# STMod.net
KiCad netlist of a schematic drawn in Altium Designer
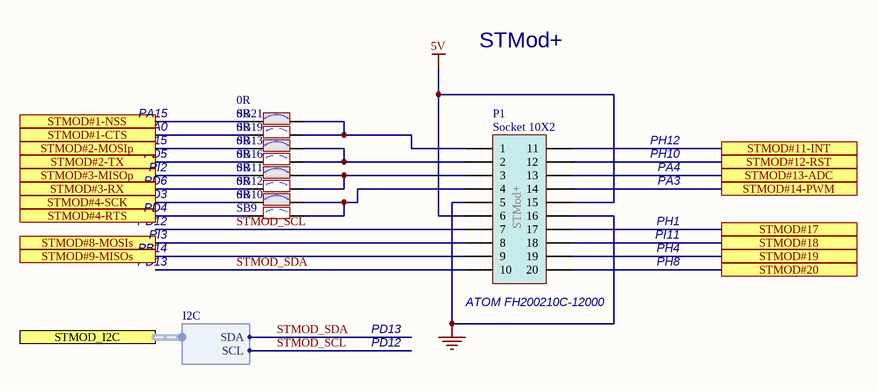
[diagram p0: STMod+.SchDoc]

(export (version "E")
  (design (tool "Eeschema 10.0.6"))
  (components
    (comp (ref "P1")
      (value "Socket 10X2")
      (footprint "CON_SAMTEC_SQT-110-01-F-D-RA__STMOD+")
      (description "Socket 10x2, 2.00mm, RA, TH, Height 6.35mm/2.29mm")
      (fields
        (field (name "INTERNAL_PART_NUMBER") "MCD-00309")
        (field (name "MANUFACTURER_PART_NUMBER") "SQT-110-01-F-D-RA")
        (field (name "PROVIDED_BY") "SubCon")
      )
      (libsource (lib "MCD_PARTS_database") (part "Socket 10X2 STMod+"))
    )
    (comp (ref "SB9")
      (value "0R")
      (footprint "SOLDER-BRIDGE_R0603-0R")
      (description "Solder Bridge OFF")
      (fields (field (name "INTERNAL_PART_NUMBER") "MCD-00072") (field (name "MANUFACTURER") "YAGEO"))
      (libsource (lib "MCD_PARTS_database") (part "SB_OFF"))
    )
    (comp (ref "SB10")
      (value "0R")
      (footprint "SOLDER-BRIDGE_R0603-0R")
      (description "Solder Bridge ON")
      (fields
        (field (name "INTERNAL_PART_NUMBER") "MCD-00071")
        (field (name "MANUFACTURER") "YAGEO")
        (field (name "PROVIDED_BY") "Subcon")
      )
      (libsource (lib "MCD_PARTS_database") (part "SB_ON"))
    )
    (comp (ref "SB11")
      (value "0R")
      (footprint "SOLDER-BRIDGE_R0603-0R")
      (description "Solder Bridge ON")
      (fields
        (field (name "INTERNAL_PART_NUMBER") "MCD-00071")
        (field (name "MANUFACTURER") "YAGEO")
        (field (name "PROVIDED_BY") "Subcon")
      )
      (libsource (lib "MCD_PARTS_database") (part "SB_ON"))
    )
    (comp (ref "SB12")
      (value "0R")
      (footprint "SOLDER-BRIDGE_R0603-0R")
      (description "Solder Bridge OFF")
      (fields (field (name "INTERNAL_PART_NUMBER") "MCD-00072") (field (name "MANUFACTURER") "YAGEO"))
      (libsource (lib "MCD_PARTS_database") (part "SB_OFF"))
    )
    (comp (ref "SB13")
      (value "0R")
      (footprint "SOLDER-BRIDGE_R0603-0R")
      (description "Solder Bridge ON")
      (fields
        (field (name "INTERNAL_PART_NUMBER") "MCD-00071")
        (field (name "MANUFACTURER") "YAGEO")
        (field (name "PROVIDED_BY") "Subcon")
      )
      (libsource (lib "MCD_PARTS_database") (part "SB_ON"))
    )
    (comp (ref "SB16")
      (value "0R")
      (footprint "SOLDER-BRIDGE_R0603-0R")
      (description "Solder Bridge OFF")
      (fields (field (name "INTERNAL_PART_NUMBER") "MCD-00072") (field (name "MANUFACTURER") "YAGEO"))
      (libsource (lib "MCD_PARTS_database") (part "SB_OFF"))
    )
    (comp (ref "SB19")
      (value "0R")
      (footprint "SOLDER-BRIDGE_R0603-0R")
      (description "Solder Bridge OFF")
      (fields (field (name "INTERNAL_PART_NUMBER") "MCD-00072") (field (name "MANUFACTURER") "YAGEO"))
      (libsource (lib "MCD_PARTS_database") (part "SB_OFF"))
    )
    (comp (ref "SB21")
      (value "0R")
      (footprint "SOLDER-BRIDGE_R0603-0R")
      (description "Solder Bridge ON")
      (fields
        (field (name "INTERNAL_PART_NUMBER") "MCD-00071")
        (field (name "MANUFACTURER") "YAGEO")
        (field (name "PROVIDED_BY") "Subcon")
      )
      (libsource (lib "MCD_PARTS_database") (part "SB_ON"))
    )
  )
  (nets
    (net (code "2") (name "/STMOD#1-CTS") (class "Default")
      (node (ref "SB19") (pin "1") (pinfunction "1_1") (pintype "passive"))
    )
    (net (code "3") (name "/STMOD#1-NSS") (class "Default")
      (node (ref "SB21") (pin "1") (pinfunction "1_1") (pintype "passive"))
    )
    (net (code "4") (name "/STMOD#2-MOSIp") (class "Default")
      (node (ref "SB13") (pin "1") (pinfunction "1_1") (pintype "passive"))
    )
    (net (code "5") (name "/STMOD#2-TX") (class "Default")
      (node (ref "SB16") (pin "1") (pinfunction "1_1") (pintype "passive"))
    )
    (net (code "6") (name "/STMOD#3-MISOp") (class "Default")
      (node (ref "SB11") (pin "1") (pinfunction "1_1") (pintype "passive"))
    )
    (net (code "7") (name "/STMOD#3-RX") (class "Default")
      (node (ref "SB12") (pin "1") (pinfunction "1_1") (pintype "passive"))
    )
    (net (code "8") (name "/STMOD#4-RTS") (class "Default")
      (node (ref "SB9") (pin "1") (pinfunction "1_1") (pintype "passive"))
    )
    (net (code "9") (name "/STMOD#4-SCK") (class "Default")
      (node (ref "SB10") (pin "1") (pinfunction "1_1") (pintype "passive"))
    )
    (net (code "10") (name "/STMOD#8-MOSIs") (class "Default")
      (node (ref "P1") (pin "8") (pinfunction "8_8") (pintype "passive"))
    )
    (net (code "11") (name "/STMOD#9-MISOs") (class "Default")
      (node (ref "P1") (pin "9") (pinfunction "9_9") (pintype "passive"))
    )
    (net (code "12") (name "/STMOD#11-INT") (class "Default")
      (node (ref "P1") (pin "11") (pinfunction "11_11") (pintype "passive"))
    )
    (net (code "13") (name "/STMOD#12-RST") (class "Default")
      (node (ref "P1") (pin "12") (pinfunction "12_12") (pintype "passive"))
    )
    (net (code "14") (name "/STMOD#13-ADC") (class "Default")
      (node (ref "P1") (pin "13") (pinfunction "13_13") (pintype "passive"))
    )
    (net (code "15") (name "/STMOD#14-PWM") (class "Default")
      (node (ref "P1") (pin "14") (pinfunction "14_14") (pintype "passive"))
    )
    (net (code "16") (name "/STMOD#17") (class "Default")
      (node (ref "P1") (pin "17") (pinfunction "17_17") (pintype "passive"))
    )
    (net (code "17") (name "/STMOD#18") (class "Default")
      (node (ref "P1") (pin "18") (pinfunction "18_18") (pintype "passive"))
    )
    (net (code "18") (name "/STMOD#19") (class "Default")
      (node (ref "P1") (pin "19") (pinfunction "19_19") (pintype "passive"))
    )
    (net (code "19") (name "/STMOD#20") (class "Default")
      (node (ref "P1") (pin "20") (pinfunction "20_20") (pintype "passive"))
    )
    (net (code "20") (name "/STMOD_SCL") (class "Default")
      (node (ref "P1") (pin "7") (pinfunction "7_7") (pintype "passive"))
    )
    (net (code "21") (name "/STMOD_SDA") (class "Default")
      (node (ref "P1") (pin "10") (pinfunction "10_10") (pintype "passive"))
    )
    (net (code "23") (name "5V") (class "Default")
      (node (ref "P1") (pin "15") (pinfunction "15_15") (pintype "passive"))
      (node (ref "P1") (pin "6") (pinfunction "6_6") (pintype "passive"))
    )
    (net (code "24") (name "GND") (class "Default")
      (node (ref "P1") (pin "16") (pinfunction "16_16") (pintype "passive"))
      (node (ref "P1") (pin "5") (pinfunction "5_5") (pintype "passive"))
    )
    (net (code "25") (name "Net-(P1-Pad1)") (class "Default")
      (node (ref "P1") (pin "1") (pinfunction "1_1") (pintype "passive"))
      (node (ref "SB19") (pin "2") (pinfunction "2_2") (pintype "passive"))
      (node (ref "SB21") (pin "2") (pinfunction "2_2") (pintype "passive"))
    )
    (net (code "26") (name "Net-(P1-Pad2)") (class "Default")
      (node (ref "P1") (pin "2") (pinfunction "2_2") (pintype "passive"))
      (node (ref "SB13") (pin "2") (pinfunction "2_2") (pintype "passive"))
      (node (ref "SB16") (pin "2") (pinfunction "2_2") (pintype "passive"))
    )
    (net (code "27") (name "Net-(P1-Pad3)") (class "Default")
      (node (ref "P1") (pin "3") (pinfunction "3_3") (pintype "passive"))
      (node (ref "SB11") (pin "2") (pinfunction "2_2") (pintype "passive"))
      (node (ref "SB12") (pin "2") (pinfunction "2_2") (pintype "passive"))
    )
    (net (code "28") (name "Net-(P1-Pad4)") (class "Default")
      (node (ref "P1") (pin "4") (pinfunction "4_4") (pintype "passive"))
      (node (ref "SB10") (pin "2") (pinfunction "2_2") (pintype "passive"))
      (node (ref "SB9") (pin "2") (pinfunction "2_2") (pintype "passive"))
    )
  )
)
